# Copy_of_USB.net
KiCad netlist of a schematic drawn in Altium Designer
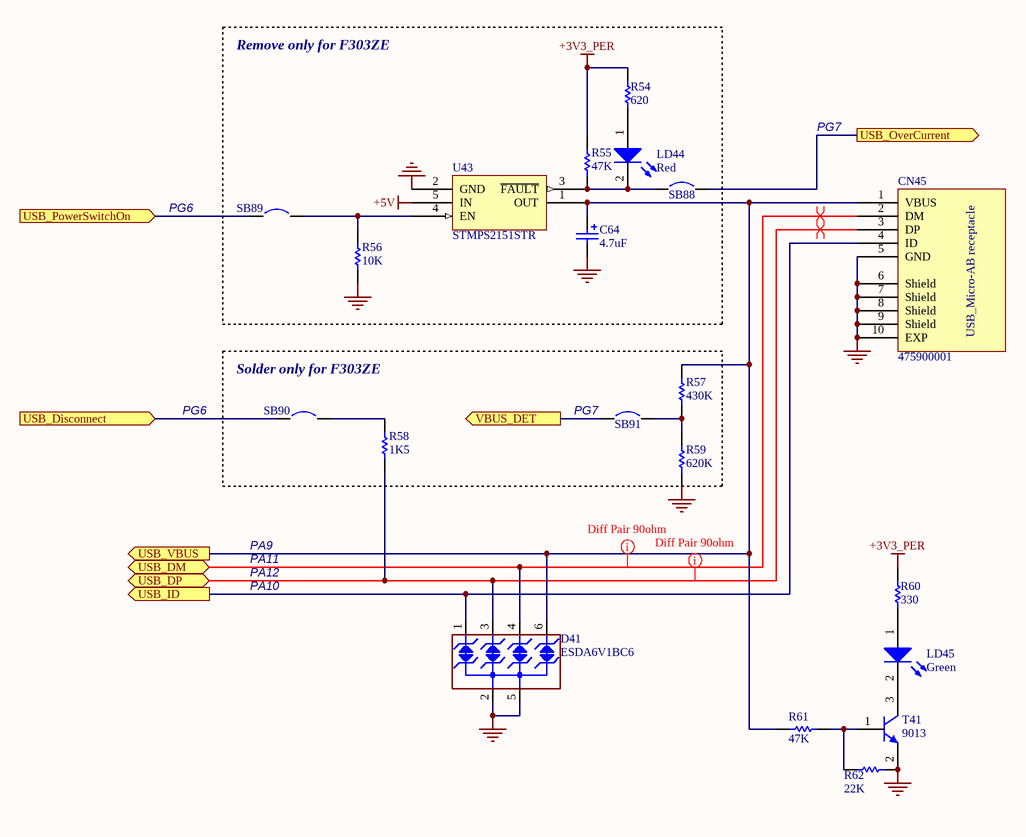
[diagram p0: Copy of USB.SchDoc]

(export (version "E")
  (design (tool "Eeschema 10.0.6"))
  (components
    (comp (ref "C64")
      (value "4.7uF")
      (footprint "TAN-A")
      (description "Polarized Capacitor (Radial)")
      (fields (field (name "PUBLISHER") "Altium Limited"))
      (libsource (lib "Miscellaneous Devices") (part "Cap Pol1"))
    )
    (comp (ref "CN45")
      (value "475900001")
      (footprint "MOLEX_47590001")
      (libsource (lib "mb1045") (part "475900001"))
    )
    (comp (ref "D41")
      (value "ESDA6V1BC6")
      (footprint "STM-SMEE:SOT23-6L")
      (description "4-line ESD protection")
      (libsource (lib "MB1137") (part "ESDA6V1BC6"))
    )
    (comp (ref "LD44")
      (value "Red")
      (footprint "0603D-R")
      (description "Typical RED, GREEN, YELLOW, AMBER GaAs LED")
      (fields (field (name "PUBLISHER") "Altium Limited"))
      (libsource (lib "Miscellaneous Devices") (part "LED2"))
    )
    (comp (ref "LD45")
      (value "Green")
      (footprint "0603D-G")
      (description "Typical RED, GREEN, YELLOW, AMBER GaAs LED")
      (fields (field (name "PUBLISHER") "Altium Limited"))
      (libsource (lib "Miscellaneous Devices") (part "LED2"))
    )
    (comp (ref "R54")
      (value "620")
      (footprint "0603R")
      (description "Resistor")
      (fields (field (name "PUBLISHER") "Altium Limited"))
      (libsource (lib "") (part "Res1_1"))
    )
    (comp (ref "R55")
      (value "47K")
      (footprint "0603R")
      (description "Resistor")
      (fields (field (name "PUBLISHER") "Altium Limited"))
      (libsource (lib "Miscellaneous Devices") (part "res1"))
    )
    (comp (ref "R56")
      (value "10K")
      (footprint "0603R")
      (description "Resistor")
      (fields (field (name "PUBLISHER") "Altium Limited"))
      (libsource (lib "") (part "Res1_1"))
    )
    (comp (ref "R57")
      (value "430K")
      (footprint "0603R")
      (description "Resistor")
      (fields (field (name "PUBLISHER") "Altium Limited"))
      (libsource (lib "Miscellaneous Devices") (part "res1"))
    )
    (comp (ref "R58")
      (value "1K5")
      (footprint "0603R")
      (description "Resistor 0402 / 0603 / 0805")
      (libsource (lib "Miscellaneous Devices") (part "Res1"))
    )
    (comp (ref "R59")
      (value "620K")
      (footprint "0603R")
      (description "Resistor")
      (fields (field (name "PUBLISHER") "Altium Limited"))
      (libsource (lib "Miscellaneous Devices") (part "res1"))
    )
    (comp (ref "R60")
      (value "330")
      (footprint "0603R")
      (description "Resistor")
      (fields (field (name "PUBLISHER") "Altium Limited"))
      (libsource (lib "Miscellaneous Devices") (part "res1"))
    )
    (comp (ref "R61")
      (value "47K")
      (footprint "0603R")
      (description "Resistor")
      (fields (field (name "PUBLISHER") "Altium Limited"))
      (libsource (lib "Miscellaneous Devices") (part "res1"))
    )
    (comp (ref "R62")
      (value "22K")
      (footprint "0603R")
      (description "Resistor")
      (fields (field (name "PUBLISHER") "Altium Limited"))
      (libsource (lib "Miscellaneous Devices") (part "res1"))
    )
    (comp (ref "SB88")
      (value "Circuit Breaker")
      (footprint "SB_0603")
      (fields (field (name "PUBLISHER") "Altium Limited"))
      (libsource (lib "MCD_TOOLS") (part "Circuit Breaker"))
    )
    (comp (ref "SB89")
      (value "Circuit Breaker")
      (footprint "SB_0603")
      (fields (field (name "PUBLISHER") "Altium Limited"))
      (libsource (lib "MCD_TOOLS") (part "Circuit Breaker"))
    )
    (comp (ref "SB90")
      (value "Circuit Breaker")
      (footprint "SB_0603")
      (fields (field (name "PUBLISHER") "Altium Limited"))
      (libsource (lib "MCD_TOOLS") (part "Circuit Breaker"))
    )
    (comp (ref "SB91")
      (value "Circuit Breaker")
      (footprint "SB_0603")
      (fields (field (name "PUBLISHER") "Altium Limited"))
      (libsource (lib "MCD_TOOLS") (part "Circuit Breaker"))
    )
    (comp (ref "T41")
      (value "9013")
      (footprint "SOT-23")
      (description "NPN Bipolar Transistor")
      (fields (field (name "PUBLISHER") "Altium Limited"))
      (libsource (lib "MB1167") (part "NPN"))
    )
    (comp (ref "U43")
      (value "STMPS2151STR")
      (footprint "SOT-23-5L")
      (libsource (lib "mb1045") (part "STMPS2141STR"))
    )
  )
  (nets
    (net (code "1") (name "+3V3_PER") (class "Default")
      (node (ref "R54") (pin "2") (pinfunction "2_2") (pintype "passive"))
      (node (ref "R55") (pin "1") (pinfunction "1_1") (pintype "passive"))
      (node (ref "R60") (pin "2") (pinfunction "2_2") (pintype "passive"))
    )
    (net (code "2") (name "+5V") (class "Default")
      (node (ref "U43") (pin "5") (pinfunction "IN_5") (pintype "passive"))
    )
    (net (code "3") (name "/USB_DM") (class "Default")
      (node (ref "CN45") (pin "2") (pinfunction "DM_2") (pintype "passive"))
      (node (ref "D41") (pin "4") (pinfunction "IO3_4") (pintype "passive"))
    )
    (net (code "4") (name "/USB_DP") (class "Default")
      (node (ref "CN45") (pin "3") (pinfunction "DP_3") (pintype "passive"))
      (node (ref "D41") (pin "3") (pinfunction "GND_3") (pintype "passive"))
      (node (ref "R58") (pin "1") (pinfunction "1_1") (pintype "passive"))
    )
    (net (code "5") (name "/USB_Disconnect") (class "Default")
      (node (ref "SB90") (pin "1") (pinfunction "1_1") (pintype "passive"))
    )
    (net (code "6") (name "/USB_ID") (class "Default")
      (node (ref "CN45") (pin "4") (pinfunction "ID_4") (pintype "passive"))
      (node (ref "D41") (pin "1") (pinfunction "IO1_1") (pintype "passive"))
    )
    (net (code "7") (name "/USB_OverCurrent") (class "Default")
      (node (ref "SB88") (pin "2") (pinfunction "2_2") (pintype "passive"))
    )
    (net (code "8") (name "/USB_PowerSwitchOn") (class "Default")
      (node (ref "SB89") (pin "1") (pinfunction "1_1") (pintype "passive"))
    )
    (net (code "9") (name "/USB_VBUS") (class "Default")
      (node (ref "C64") (pin "1") (pinfunction "1_1") (pintype "passive"))
      (node (ref "CN45") (pin "1") (pinfunction "VBUS_1") (pintype "passive"))
      (node (ref "D41") (pin "6") (pinfunction "NC_6") (pintype "passive"))
      (node (ref "R57") (pin "1") (pinfunction "1_1") (pintype "passive"))
      (node (ref "R61") (pin "1") (pinfunction "1_1") (pintype "passive"))
      (node (ref "U43") (pin "1") (pinfunction "OUT_1") (pintype "passive"))
    )
    (net (code "10") (name "/VBUS_DET") (class "Default")
      (node (ref "SB91") (pin "1") (pinfunction "1_1") (pintype "passive"))
    )
    (net (code "11") (name "GND") (class "Default")
      (node (ref "C64") (pin "2") (pinfunction "2_2") (pintype "passive"))
      (node (ref "CN45") (pin "10") (pinfunction "EXP_10") (pintype "passive"))
      (node (ref "CN45") (pin "5") (pinfunction "GND_5") (pintype "passive"))
      (node (ref "CN45") (pin "6") (pinfunction "Shield_6") (pintype "passive"))
      (node (ref "CN45") (pin "7") (pinfunction "Shield_7") (pintype "passive"))
      (node (ref "CN45") (pin "8") (pinfunction "Shield_8") (pintype "passive"))
      (node (ref "CN45") (pin "9") (pinfunction "Shield_9") (pintype "passive"))
      (node (ref "D41") (pin "2") (pinfunction "IO2_2") (pintype "passive"))
      (node (ref "D41") (pin "5") (pinfunction "IO4_5") (pintype "passive"))
      (node (ref "R56") (pin "1") (pinfunction "1_1") (pintype "passive"))
      (node (ref "R59") (pin "2") (pinfunction "2_2") (pintype "passive"))
      (node (ref "R62") (pin "1") (pinfunction "1_1") (pintype "passive"))
      (node (ref "T41") (pin "2") (pinfunction "E_2") (pintype "passive"))
      (node (ref "U43") (pin "2") (pinfunction "GND_2") (pintype "passive"))
    )
    (net (code "12") (name "Net-(LD44-A)") (class "Default")
      (node (ref "LD44") (pin "1") (pinfunction "A_1") (pintype "passive"))
      (node (ref "R54") (pin "1") (pinfunction "1_1") (pintype "passive"))
    )
    (net (code "13") (name "Net-(LD44-K)") (class "Default")
      (node (ref "LD44") (pin "2") (pinfunction "K_2") (pintype "passive"))
      (node (ref "R55") (pin "2") (pinfunction "2_2") (pintype "passive"))
      (node (ref "SB88") (pin "1") (pinfunction "1_1") (pintype "passive"))
      (node (ref "U43") (pin "3") (pinfunction "~{FAULT}_3") (pintype "output"))
    )
    (net (code "14") (name "Net-(LD45-A)") (class "Default")
      (node (ref "LD45") (pin "1") (pinfunction "A_1") (pintype "passive"))
      (node (ref "R60") (pin "1") (pinfunction "1_1") (pintype "passive"))
    )
    (net (code "15") (name "Net-(LD45-K)") (class "Default")
      (node (ref "LD45") (pin "2") (pinfunction "K_2") (pintype "passive"))
      (node (ref "T41") (pin "3") (pinfunction "C_3") (pintype "passive"))
    )
    (net (code "16") (name "Net-(R57-Pad2)") (class "Default")
      (node (ref "R57") (pin "2") (pinfunction "2_2") (pintype "passive"))
      (node (ref "R59") (pin "1") (pinfunction "1_1") (pintype "passive"))
      (node (ref "SB91") (pin "2") (pinfunction "2_2") (pintype "passive"))
    )
    (net (code "17") (name "Net-(R58-Pad2)") (class "Default")
      (node (ref "R58") (pin "2") (pinfunction "2_2") (pintype "passive"))
      (node (ref "SB90") (pin "2") (pinfunction "2_2") (pintype "passive"))
    )
    (net (code "18") (name "Net-(T41-B)") (class "Default")
      (node (ref "R61") (pin "2") (pinfunction "2_2") (pintype "passive"))
      (node (ref "R62") (pin "2") (pinfunction "2_2") (pintype "passive"))
      (node (ref "T41") (pin "1") (pinfunction "B_1") (pintype "passive"))
    )
    (net (code "19") (name "Net-(U43-EN)") (class "Default")
      (node (ref "R56") (pin "2") (pinfunction "2_2") (pintype "passive"))
      (node (ref "SB89") (pin "2") (pinfunction "2_2") (pintype "passive"))
      (node (ref "U43") (pin "4") (pinfunction "EN_4") (pintype "input"))
    )
  )
)
